# ESP8266.net
KiCad netlist of a schematic drawn in EAGLE
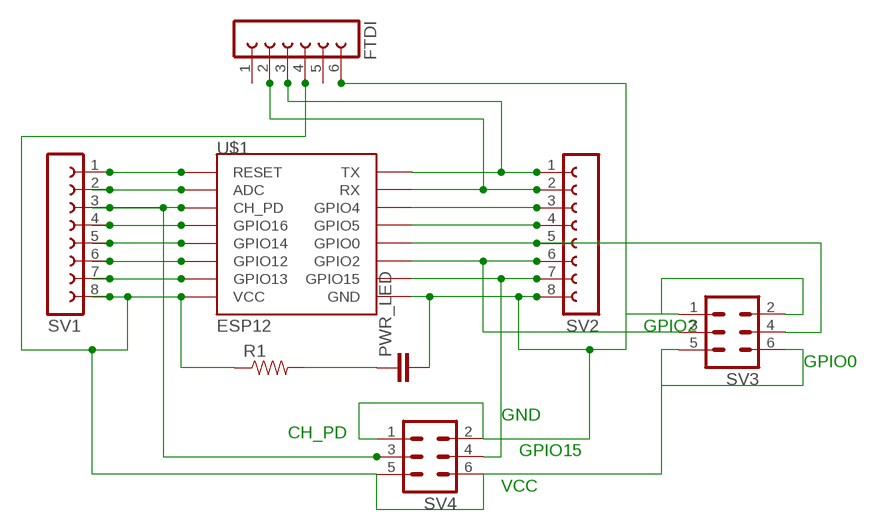
[diagram p0: schematic, sheet 1]

(export (version "E")
  (design (tool "Eeschema 10.0.6"))
  (components
    (comp (ref "FTDI")
      (value "FE06-1")
      (footprint "eagle-import:FE06")
      (libsource (lib "eagle-import") (part "FE06-1"))
    )
    (comp (ref "PWR_LED")
      (value "CAP0805")
      (footprint "eagle-import:0805")
      (libsource (lib "eagle-import") (part "CAP0805"))
    )
    (comp (ref "R1")
      (value "RESISTOR0805-RES")
      (footprint "eagle-import:0805")
      (libsource (lib "eagle-import") (part "RESISTOR0805-RES"))
    )
    (comp (ref "SV1")
      (value "FE08-1")
      (footprint "eagle-import:FE08")
      (libsource (lib "eagle-import") (part "FE08-1"))
    )
    (comp (ref "SV2")
      (value "FE08-1")
      (footprint "eagle-import:FE08")
      (libsource (lib "eagle-import") (part "FE08-1"))
    )
    (comp (ref "SV3")
      (value "MA03-2")
      (footprint "eagle-import:MA03-2")
      (libsource (lib "eagle-import") (part "MA03-2"))
    )
    (comp (ref "SV4")
      (value "MA03-2")
      (footprint "eagle-import:MA03-2")
      (libsource (lib "eagle-import") (part "MA03-2"))
    )
    (comp (ref "U$1")
      (value "ESP12")
      (footprint "eagle-import:ESP12")
      (libsource (lib "eagle-import") (part "ESP12"))
    )
  )
  (nets
    (net (code "1") (name "Net-(FTDI-Pad2)") (class "Default")
      (node (ref "FTDI") (pin "2") (pinfunction "2_2") (pintype "passive"))
      (node (ref "SV2") (pin "2") (pinfunction "2_2") (pintype "passive"))
      (node (ref "U$1") (pin "RX") (pinfunction "RX_RX") (pintype "bidirectional"))
    )
    (net (code "2") (name "Net-(FTDI-Pad3)") (class "Default")
      (node (ref "FTDI") (pin "3") (pinfunction "3_3") (pintype "passive"))
      (node (ref "SV2") (pin "1") (pinfunction "1_1") (pintype "passive"))
      (node (ref "U$1") (pin "TX") (pinfunction "TX_TX") (pintype "bidirectional"))
    )
    (net (code "3") (name "Net-(FTDI-Pad4)") (class "Default")
      (node (ref "FTDI") (pin "4") (pinfunction "4_4") (pintype "passive"))
      (node (ref "R1") (pin "1") (pinfunction "1_1") (pintype "passive"))
      (node (ref "SV1") (pin "8") (pinfunction "8_8") (pintype "passive"))
      (node (ref "SV3") (pin "5") (pinfunction "5_5") (pintype "passive"))
      (node (ref "SV3") (pin "6") (pinfunction "6_6") (pintype "passive"))
      (node (ref "SV4") (pin "5") (pinfunction "5_5") (pintype "passive"))
      (node (ref "SV4") (pin "6") (pinfunction "6_6") (pintype "passive"))
      (node (ref "U$1") (pin "VCC") (pinfunction "VCC_VCC") (pintype "bidirectional"))
    )
    (net (code "4") (name "Net-(FTDI-Pad6)") (class "Default")
      (node (ref "FTDI") (pin "6") (pinfunction "6_6") (pintype "passive"))
      (node (ref "PWR_LED") (pin "2") (pinfunction "2_2") (pintype "passive"))
      (node (ref "SV2") (pin "8") (pinfunction "8_8") (pintype "passive"))
      (node (ref "SV3") (pin "1") (pinfunction "1_1") (pintype "passive"))
      (node (ref "SV3") (pin "2") (pinfunction "2_2") (pintype "passive"))
      (node (ref "SV4") (pin "1") (pinfunction "1_1") (pintype "passive"))
      (node (ref "SV4") (pin "2") (pinfunction "2_2") (pintype "passive"))
      (node (ref "U$1") (pin "GND") (pinfunction "GND_GND") (pintype "bidirectional"))
    )
    (net (code "5") (name "Net-(PWR_LED-Pad1)") (class "Default")
      (node (ref "PWR_LED") (pin "1") (pinfunction "1_1") (pintype "passive"))
      (node (ref "R1") (pin "2") (pinfunction "2_2") (pintype "passive"))
    )
    (net (code "6") (name "Net-(SV1-Pad1)") (class "Default")
      (node (ref "SV1") (pin "1") (pinfunction "1_1") (pintype "passive"))
      (node (ref "U$1") (pin "RESET") (pinfunction "RESET_RESET") (pintype "bidirectional"))
    )
    (net (code "7") (name "Net-(SV1-Pad2)") (class "Default")
      (node (ref "SV1") (pin "2") (pinfunction "2_2") (pintype "passive"))
      (node (ref "U$1") (pin "ADC") (pinfunction "ADC_ADC") (pintype "bidirectional"))
    )
    (net (code "8") (name "Net-(SV1-Pad3)") (class "Default")
      (node (ref "SV1") (pin "3") (pinfunction "3_3") (pintype "passive"))
      (node (ref "SV4") (pin "3") (pinfunction "3_3") (pintype "passive"))
      (node (ref "U$1") (pin "CH_PD") (pinfunction "CH_PD_CH_PD") (pintype "bidirectional"))
    )
    (net (code "9") (name "Net-(SV1-Pad4)") (class "Default")
      (node (ref "SV1") (pin "4") (pinfunction "4_4") (pintype "passive"))
      (node (ref "U$1") (pin "GPIO16") (pinfunction "GPIO16_GPIO16") (pintype "bidirectional"))
    )
    (net (code "10") (name "Net-(SV1-Pad5)") (class "Default")
      (node (ref "SV1") (pin "5") (pinfunction "5_5") (pintype "passive"))
      (node (ref "U$1") (pin "GPIO14") (pinfunction "GPIO14_GPIO14") (pintype "bidirectional"))
    )
    (net (code "11") (name "Net-(SV1-Pad6)") (class "Default")
      (node (ref "SV1") (pin "6") (pinfunction "6_6") (pintype "passive"))
      (node (ref "U$1") (pin "GPIO12") (pinfunction "GPIO12_GPIO12") (pintype "bidirectional"))
    )
    (net (code "12") (name "Net-(SV1-Pad7)") (class "Default")
      (node (ref "SV1") (pin "7") (pinfunction "7_7") (pintype "passive"))
      (node (ref "U$1") (pin "GPIO13") (pinfunction "GPIO13_GPIO13") (pintype "bidirectional"))
    )
    (net (code "13") (name "Net-(SV2-Pad3)") (class "Default")
      (node (ref "SV2") (pin "3") (pinfunction "3_3") (pintype "passive"))
      (node (ref "U$1") (pin "GPIO4") (pinfunction "GPIO4_GPIO4") (pintype "bidirectional"))
    )
    (net (code "14") (name "Net-(SV2-Pad4)") (class "Default")
      (node (ref "SV2") (pin "4") (pinfunction "4_4") (pintype "passive"))
      (node (ref "U$1") (pin "GPIO5") (pinfunction "GPIO5_GPIO5") (pintype "bidirectional"))
    )
    (net (code "15") (name "Net-(SV2-Pad5)") (class "Default")
      (node (ref "SV2") (pin "5") (pinfunction "5_5") (pintype "passive"))
      (node (ref "SV3") (pin "4") (pinfunction "4_4") (pintype "passive"))
      (node (ref "U$1") (pin "GPIO0") (pinfunction "GPIO0_GPIO0") (pintype "bidirectional"))
    )
    (net (code "16") (name "Net-(SV2-Pad6)") (class "Default")
      (node (ref "SV2") (pin "6") (pinfunction "6_6") (pintype "passive"))
      (node (ref "SV3") (pin "3") (pinfunction "3_3") (pintype "passive"))
      (node (ref "U$1") (pin "GPIO2") (pinfunction "GPIO2_GPIO2") (pintype "bidirectional"))
    )
    (net (code "17") (name "Net-(SV2-Pad7)") (class "Default")
      (node (ref "SV2") (pin "7") (pinfunction "7_7") (pintype "passive"))
      (node (ref "SV4") (pin "4") (pinfunction "4_4") (pintype "passive"))
      (node (ref "U$1") (pin "GPIO15") (pinfunction "GPIO15_GPIO15") (pintype "bidirectional"))
    )
    (net (code "18") (name "unconnected-(FTDI-Pad1)") (class "Default")
      (node (ref "FTDI") (pin "1") (pinfunction "1_1") (pintype "passive"))
    )
    (net (code "19") (name "unconnected-(FTDI-Pad5)") (class "Default")
      (node (ref "FTDI") (pin "5") (pinfunction "5_5") (pintype "passive"))
    )
  )
)
